# Sound.net
KiCad netlist of a schematic drawn in Altium Designer
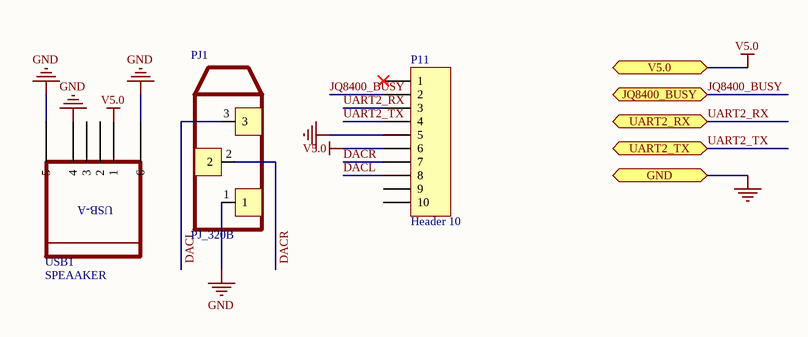
[diagram p0: Sound.SchDoc]

(export (version "E")
  (design (tool "Eeschema 10.0.6"))
  (components
    (comp (ref "P11")
      (value "Header 10")
      (footprint "HDR1X10")
      (description "Header, 10-Pin")
      (fields (field (name "PUBLISHER") "Altium Limited"))
      (libsource (lib "Miscellaneous Connectors") (part "Header 10"))
    )
    (comp (ref "PJ1") (value "PJ_320B") (footprint "PJ-320B") (libsource (lib "mylib") (part "PJ_320B")))
    (comp (ref "USB1") (value "SPEAAKER") (footprint "USB-A") (libsource (lib "mylib") (part "USB-A")))
  )
  (nets
    (net (code "1") (name "/DACL") (class "Default")
      (node (ref "P11") (pin "8") (pinfunction "8_8") (pintype "passive"))
      (node (ref "PJ1") (pin "3") (pinfunction "3_3") (pintype "passive"))
    )
    (net (code "2") (name "/DACR") (class "Default")
      (node (ref "P11") (pin "7") (pinfunction "7_7") (pintype "passive"))
      (node (ref "PJ1") (pin "2") (pinfunction "2_2") (pintype "passive"))
    )
    (net (code "3") (name "/JQ8400_BUSY") (class "Default")
      (node (ref "P11") (pin "2") (pinfunction "2_2") (pintype "passive"))
    )
    (net (code "4") (name "/UART2_RX") (class "Default")
      (node (ref "P11") (pin "3") (pinfunction "3_3") (pintype "passive"))
    )
    (net (code "5") (name "/UART2_TX") (class "Default")
      (node (ref "P11") (pin "4") (pinfunction "4_4") (pintype "passive"))
    )
    (net (code "6") (name "GND") (class "Default")
      (node (ref "P11") (pin "5") (pinfunction "5_5") (pintype "passive"))
      (node (ref "PJ1") (pin "1") (pinfunction "1_1") (pintype "passive"))
      (node (ref "USB1") (pin "4") (pinfunction "4_4") (pintype "passive"))
      (node (ref "USB1") (pin "5") (pinfunction "5_5") (pintype "passive"))
      (node (ref "USB1") (pin "6") (pinfunction "6_6") (pintype "passive"))
    )
    (net (code "7") (name "V5.0") (class "Default")
      (node (ref "P11") (pin "6") (pinfunction "6_6") (pintype "passive"))
      (node (ref "USB1") (pin "1") (pinfunction "1_1") (pintype "passive"))
    )
    (net (code "8") (name "unconnected-(P11-Pad1)") (class "Default")
      (node (ref "P11") (pin "1") (pinfunction "1_1") (pintype "passive+no_connect"))
    )
    (net (code "9") (name "unconnected-(P11-Pad9)") (class "Default")
      (node (ref "P11") (pin "9") (pinfunction "9_9") (pintype "passive"))
    )
    (net (code "10") (name "unconnected-(P11-Pad10)") (class "Default")
      (node (ref "P11") (pin "10") (pinfunction "10_10") (pintype "passive"))
    )
    (net (code "11") (name "unconnected-(USB1-Pad2)") (class "Default")
      (node (ref "USB1") (pin "2") (pinfunction "2_2") (pintype "passive"))
    )
    (net (code "12") (name "unconnected-(USB1-Pad3)") (class "Default")
      (node (ref "USB1") (pin "3") (pinfunction "3_3") (pintype "passive"))
    )
  )
)
